# BrickPi_0_7.net
KiCad netlist of a schematic drawn in EAGLE
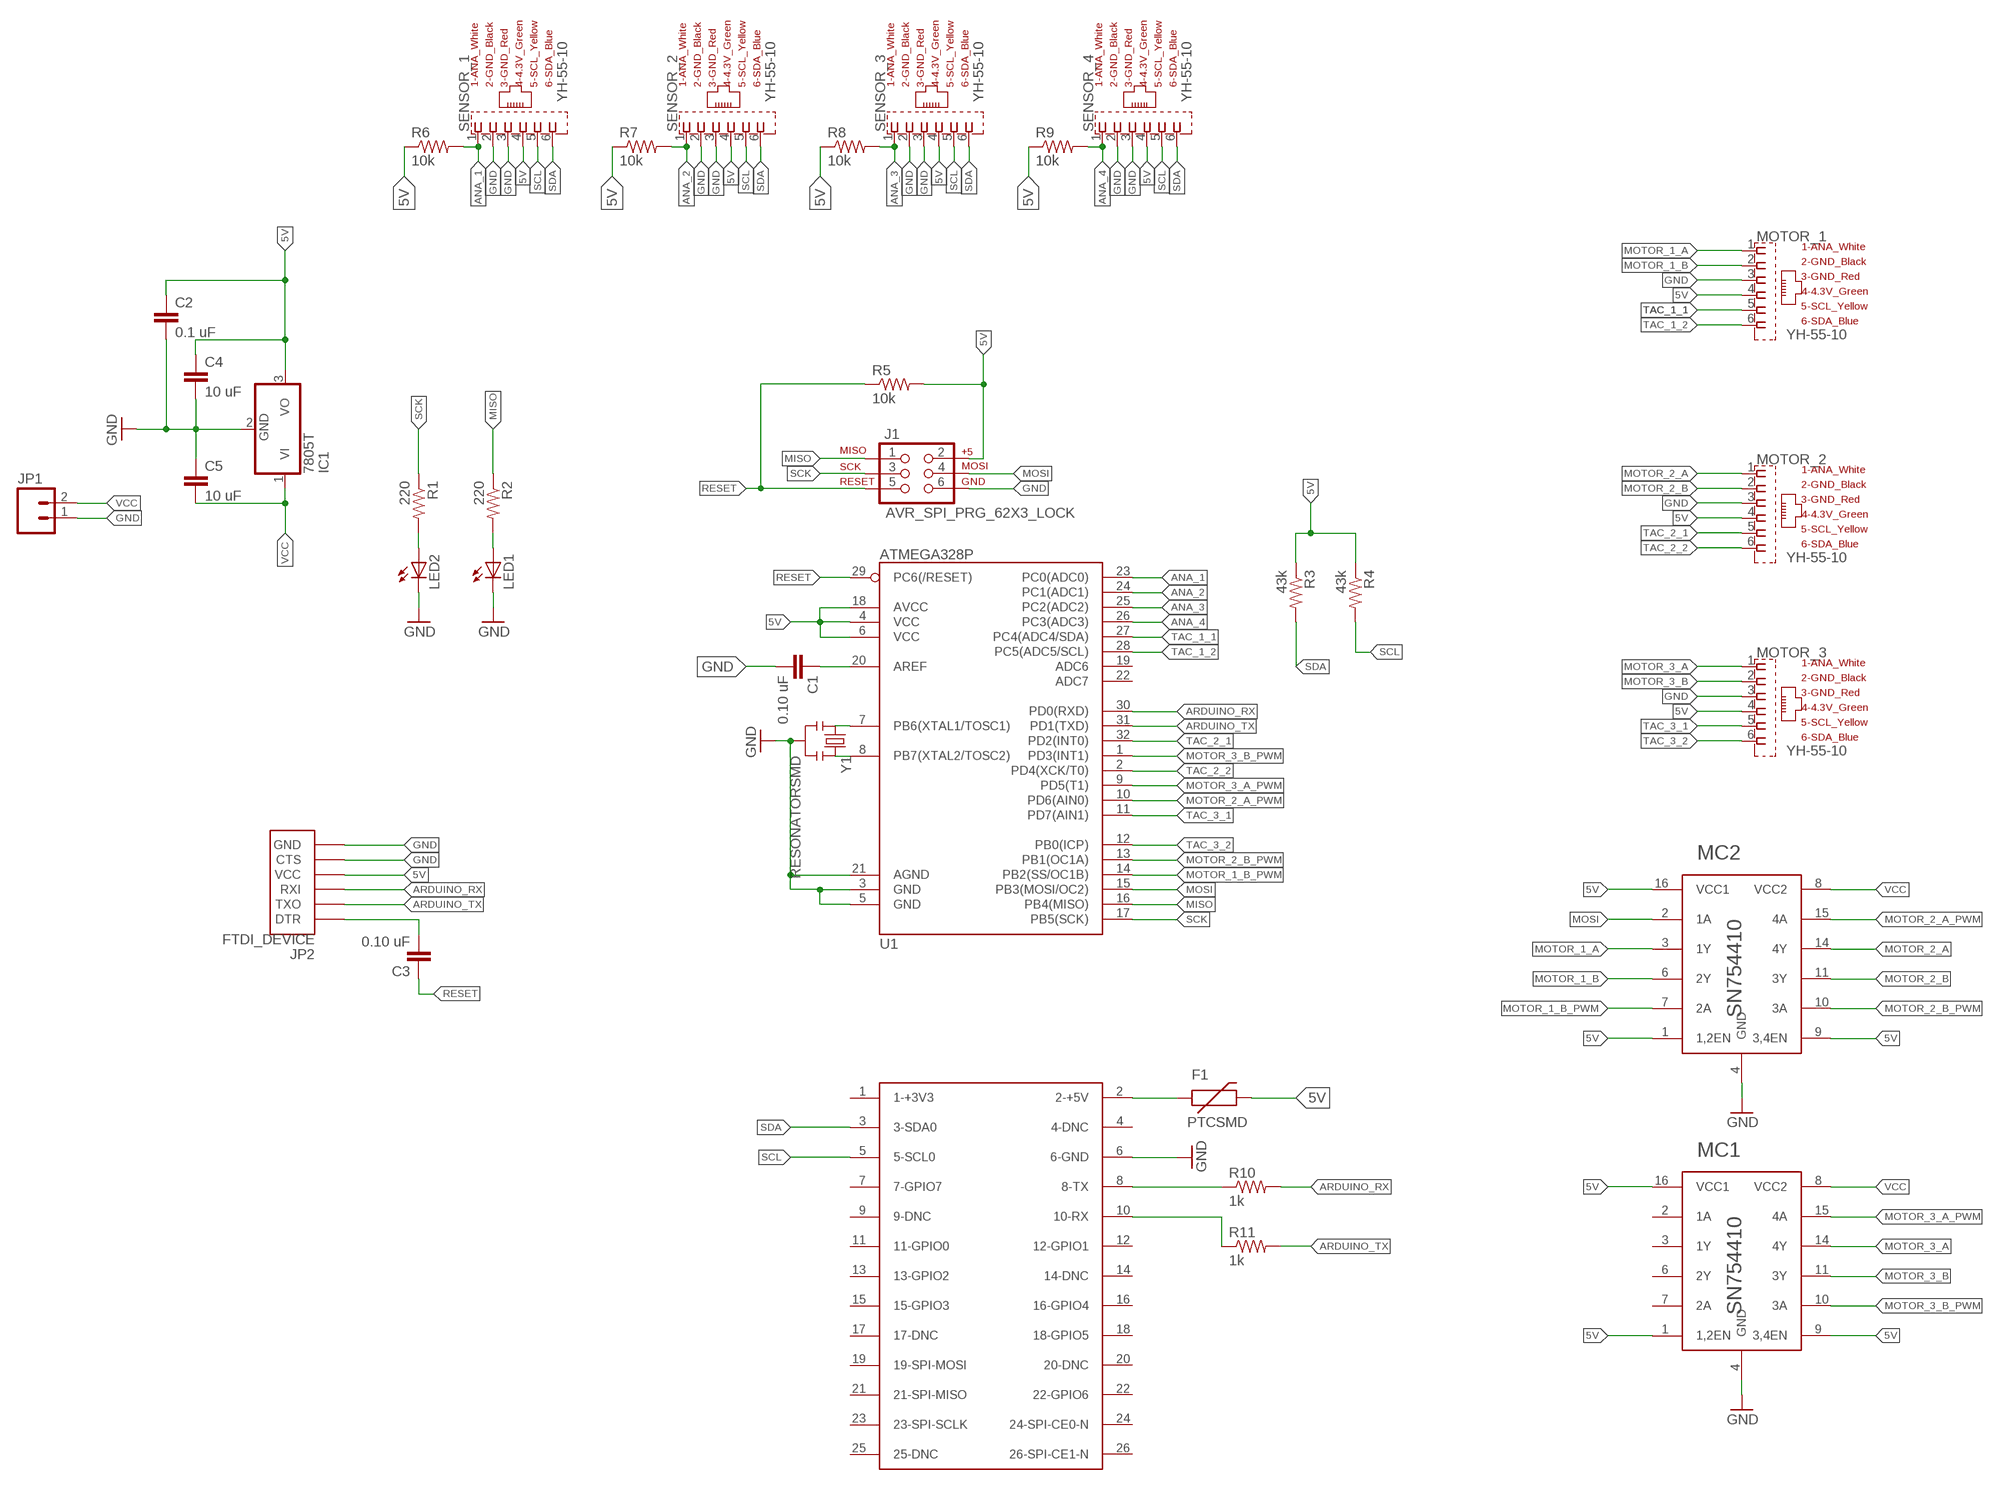
[diagram p0: schematic, sheet 1]

(export (version "E")
  (design (tool "Eeschema 10.0.6"))
  (components
    (comp (ref "C1")
      (value "0.10 uF")
      (footprint "eagle-import:0805")
      (libsource (lib "eagle-import") (part "CAP0805"))
    )
    (comp (ref "C2")
      (value "0.1 uF")
      (footprint "eagle-import:0805")
      (libsource (lib "eagle-import") (part "CAP0805"))
    )
    (comp (ref "C3")
      (value "0.10 uF")
      (footprint "eagle-import:0805")
      (libsource (lib "eagle-import") (part "CAP0805"))
    )
    (comp (ref "C4")
      (value "10 uF")
      (footprint "eagle-import:0805")
      (libsource (lib "eagle-import") (part "CAP0805"))
    )
    (comp (ref "C5")
      (value "10 uF")
      (footprint "eagle-import:0805")
      (libsource (lib "eagle-import") (part "CAP0805"))
    )
    (comp (ref "F1")
      (value "PTCSMD")
      (footprint "eagle-import:PTC-1206")
      (libsource (lib "eagle-import") (part "PTCSMD"))
    )
    (comp (ref "IC1")
      (value "7805T")
      (footprint "eagle-import:TO220H")
      (libsource (lib "eagle-import") (part "78T05"))
    )
    (comp (ref "J1")
      (value "AVR_SPI_PRG_62X3_LOCK")
      (footprint "eagle-import:2X3_LOCK")
      (libsource (lib "eagle-import") (part "AVR_SPI_PRG_62X3_LOCK"))
    )
    (comp (ref "JP1")
      (value "M02LOCK")
      (footprint "eagle-import:1X02_LOCK")
      (libsource (lib "eagle-import") (part "M02LOCK"))
    )
    (comp (ref "JP2")
      (value "FTDI_DEVICE")
      (footprint "eagle-import:FTDI_DEVICE_SIDE")
      (libsource (lib "eagle-import") (part "FTDI_DEVICE"))
    )
    (comp (ref "LED1")
      (value "LED1206")
      (footprint "eagle-import:LED-1206")
      (libsource (lib "eagle-import") (part "LED1206"))
    )
    (comp (ref "LED2")
      (value "LED1206")
      (footprint "eagle-import:LED-1206")
      (libsource (lib "eagle-import") (part "LED1206"))
    )
    (comp (ref "MC1")
      (value "SN754410")
      (footprint "eagle-import:DIL16")
      (libsource (lib "eagle-import") (part "SN754410"))
    )
    (comp (ref "MC2")
      (value "SN754410")
      (footprint "eagle-import:DIL16")
      (libsource (lib "eagle-import") (part "SN754410"))
    )
    (comp (ref "MOTOR_1")
      (value "YH-55-10")
      (footprint "eagle-import:YH-55-10")
      (libsource (lib "eagle-import") (part "YH-55-10"))
    )
    (comp (ref "MOTOR_2")
      (value "YH-55-10")
      (footprint "eagle-import:YH-55-10")
      (libsource (lib "eagle-import") (part "YH-55-10"))
    )
    (comp (ref "MOTOR_3")
      (value "YH-55-10")
      (footprint "eagle-import:YH-55-10")
      (libsource (lib "eagle-import") (part "YH-55-10"))
    )
    (comp (ref "PI_OUTLINE")
      (value "RASPBERRY-PI")
      (footprint "eagle-import:RASPBERRY-PI")
      (libsource (lib "eagle-import") (part "RASPBERRY-PI"))
    )
    (comp (ref "R1")
      (value "220")
      (footprint "eagle-import:0603-RES")
      (libsource (lib "eagle-import") (part "220-5%"))
    )
    (comp (ref "R2")
      (value "220")
      (footprint "eagle-import:0603-RES")
      (libsource (lib "eagle-import") (part "220-5%"))
    )
    (comp (ref "R3")
      (value "43k")
      (footprint "eagle-import:0603-RES")
      (fields (field (name "PROD_ID") "RES-07866"))
      (libsource (lib "eagle-import") (part "220-5%"))
    )
    (comp (ref "R4")
      (value "43k")
      (footprint "eagle-import:0603-RES")
      (fields (field (name "PROD_ID") "RES-07866"))
      (libsource (lib "eagle-import") (part "220-5%"))
    )
    (comp (ref "R5")
      (value "10k")
      (footprint "eagle-import:0603-RES")
      (fields (field (name "PROD_ID") "RES-07866"))
      (libsource (lib "eagle-import") (part "220-5%"))
    )
    (comp (ref "R6")
      (value "10k")
      (footprint "eagle-import:0603-RES")
      (fields (field (name "PROD_ID") "RES-07866"))
      (libsource (lib "eagle-import") (part "220-5%"))
    )
    (comp (ref "R7")
      (value "10k")
      (footprint "eagle-import:0603-RES")
      (fields (field (name "PROD_ID") "RES-07866"))
      (libsource (lib "eagle-import") (part "220-5%"))
    )
    (comp (ref "R8")
      (value "10k")
      (footprint "eagle-import:0603-RES")
      (fields (field (name "PROD_ID") "RES-07866"))
      (libsource (lib "eagle-import") (part "220-5%"))
    )
    (comp (ref "R9")
      (value "10k")
      (footprint "eagle-import:0603-RES")
      (fields (field (name "PROD_ID") "RES-07866"))
      (libsource (lib "eagle-import") (part "220-5%"))
    )
    (comp (ref "R10")
      (value "1k")
      (footprint "eagle-import:0603-RES")
      (fields (field (name "PROD_ID") "RES-07866"))
      (libsource (lib "eagle-import") (part "220-5%"))
    )
    (comp (ref "R11")
      (value "1k")
      (footprint "eagle-import:0603-RES")
      (fields (field (name "PROD_ID") "RES-07866"))
      (libsource (lib "eagle-import") (part "220-5%"))
    )
    (comp (ref "SENSOR_1")
      (value "YH-55-10")
      (footprint "eagle-import:YH-55-10")
      (libsource (lib "eagle-import") (part "YH-55-10"))
    )
    (comp (ref "SENSOR_2")
      (value "YH-55-10")
      (footprint "eagle-import:YH-55-10")
      (libsource (lib "eagle-import") (part "YH-55-10"))
    )
    (comp (ref "SENSOR_3")
      (value "YH-55-10")
      (footprint "eagle-import:YH-55-10")
      (libsource (lib "eagle-import") (part "YH-55-10"))
    )
    (comp (ref "SENSOR_4")
      (value "YH-55-10")
      (footprint "eagle-import:YH-55-10")
      (libsource (lib "eagle-import") (part "YH-55-10"))
    )
    (comp (ref "U1")
      (value "ATMEGA328P")
      (footprint "eagle-import:TQFP32-08")
      (libsource (lib "eagle-import") (part "ATMEGA328_SMT"))
    )
    (comp (ref "Y1")
      (value "RESONATORSMD")
      (footprint "eagle-import:RESONATOR-SMD")
      (libsource (lib "eagle-import") (part "RESONATORSMD"))
    )
  )
  (nets
    (net (code "1") (name "5V") (class "Default")
      (node (ref "C2") (pin "1") (pinfunction "1_1") (pintype "passive"))
      (node (ref "C4") (pin "1") (pinfunction "1_1") (pintype "passive"))
      (node (ref "F1") (pin "2") (pinfunction "2_2") (pintype "bidirectional"))
      (node (ref "IC1") (pin "3") (pinfunction "VO_3") (pintype "passive"))
      (node (ref "J1") (pin "2") (pinfunction "2_2") (pintype "passive"))
      (node (ref "JP2") (pin "P$4") (pinfunction "VCC_P$4") (pintype "bidirectional"))
      (node (ref "MC1") (pin "1") (pinfunction "1,2EN_1") (pintype "bidirectional"))
      (node (ref "MC1") (pin "16") (pinfunction "VCC1_16") (pintype "power_in"))
      (node (ref "MC1") (pin "9") (pinfunction "3,4EN_9") (pintype "bidirectional"))
      (node (ref "MC2") (pin "1") (pinfunction "1,2EN_1") (pintype "bidirectional"))
      (node (ref "MC2") (pin "16") (pinfunction "VCC1_16") (pintype "power_in"))
      (node (ref "MC2") (pin "9") (pinfunction "3,4EN_9") (pintype "bidirectional"))
      (node (ref "MOTOR_1") (pin "4") (pinfunction "4_4.3V_GREEN_4") (pintype "passive"))
      (node (ref "MOTOR_2") (pin "4") (pinfunction "4_4.3V_GREEN_4") (pintype "passive"))
      (node (ref "MOTOR_3") (pin "4") (pinfunction "4_4.3V_GREEN_4") (pintype "passive"))
      (node (ref "R3") (pin "1") (pinfunction "1_1") (pintype "passive"))
      (node (ref "R4") (pin "1") (pinfunction "1_1") (pintype "passive"))
      (node (ref "R5") (pin "2") (pinfunction "2_2") (pintype "passive"))
      (node (ref "R6") (pin "1") (pinfunction "1_1") (pintype "passive"))
      (node (ref "R7") (pin "1") (pinfunction "1_1") (pintype "passive"))
      (node (ref "R8") (pin "1") (pinfunction "1_1") (pintype "passive"))
      (node (ref "R9") (pin "1") (pinfunction "1_1") (pintype "passive"))
      (node (ref "SENSOR_1") (pin "4") (pinfunction "4_4.3V_GREEN_4") (pintype "passive"))
      (node (ref "SENSOR_2") (pin "4") (pinfunction "4_4.3V_GREEN_4") (pintype "passive"))
      (node (ref "SENSOR_3") (pin "4") (pinfunction "4_4.3V_GREEN_4") (pintype "passive"))
      (node (ref "SENSOR_4") (pin "4") (pinfunction "4_4.3V_GREEN_4") (pintype "passive"))
      (node (ref "U1") (pin "18") (pinfunction "AVCC_18") (pintype "bidirectional"))
      (node (ref "U1") (pin "4") (pinfunction "VCC_4") (pintype "bidirectional"))
      (node (ref "U1") (pin "6") (pinfunction "VCC_6") (pintype "bidirectional"))
    )
    (net (code "2") (name "ANA_1") (class "Default")
      (node (ref "R6") (pin "2") (pinfunction "2_2") (pintype "passive"))
      (node (ref "SENSOR_1") (pin "1") (pinfunction "1_ANA_WHITE_1") (pintype "passive"))
      (node (ref "U1") (pin "23") (pinfunction "PC0(ADC0)_23") (pintype "bidirectional"))
    )
    (net (code "3") (name "ANA_2") (class "Default")
      (node (ref "R7") (pin "2") (pinfunction "2_2") (pintype "passive"))
      (node (ref "SENSOR_2") (pin "1") (pinfunction "1_ANA_WHITE_1") (pintype "passive"))
      (node (ref "U1") (pin "24") (pinfunction "PC1(ADC1)_24") (pintype "bidirectional"))
    )
    (net (code "4") (name "ANA_3") (class "Default")
      (node (ref "R8") (pin "2") (pinfunction "2_2") (pintype "passive"))
      (node (ref "SENSOR_3") (pin "1") (pinfunction "1_ANA_WHITE_1") (pintype "passive"))
      (node (ref "U1") (pin "25") (pinfunction "PC2(ADC2)_25") (pintype "bidirectional"))
    )
    (net (code "5") (name "ANA_4") (class "Default")
      (node (ref "R9") (pin "2") (pinfunction "2_2") (pintype "passive"))
      (node (ref "SENSOR_4") (pin "1") (pinfunction "1_ANA_WHITE_1") (pintype "passive"))
      (node (ref "U1") (pin "26") (pinfunction "PC3(ADC3)_26") (pintype "bidirectional"))
    )
    (net (code "6") (name "ARDUINO_RX") (class "Default")
      (node (ref "JP2") (pin "P$3") (pinfunction "RXI_P$3") (pintype "bidirectional"))
      (node (ref "R10") (pin "2") (pinfunction "2_2") (pintype "passive"))
      (node (ref "U1") (pin "30") (pinfunction "PD0(RXD)_30") (pintype "bidirectional"))
    )
    (net (code "7") (name "ARDUINO_TX") (class "Default")
      (node (ref "JP2") (pin "P$2") (pinfunction "TXO_P$2") (pintype "bidirectional"))
      (node (ref "R11") (pin "2") (pinfunction "2_2") (pintype "passive"))
      (node (ref "U1") (pin "31") (pinfunction "PD1(TXD)_31") (pintype "bidirectional"))
    )
    (net (code "8") (name "GND") (class "Default")
      (node (ref "C1") (pin "2") (pinfunction "2_2") (pintype "passive"))
      (node (ref "C2") (pin "2") (pinfunction "2_2") (pintype "passive"))
      (node (ref "C4") (pin "2") (pinfunction "2_2") (pintype "passive"))
      (node (ref "C5") (pin "1") (pinfunction "1_1") (pintype "passive"))
      (node (ref "IC1") (pin "2") (pinfunction "GND_2") (pintype "passive"))
      (node (ref "J1") (pin "6") (pinfunction "6_6") (pintype "passive"))
      (node (ref "JP1") (pin "1") (pinfunction "1_1") (pintype "passive"))
      (node (ref "JP2") (pin "P$5") (pinfunction "CTS_P$5") (pintype "bidirectional"))
      (node (ref "JP2") (pin "P$6") (pinfunction "GND_P$6") (pintype "bidirectional"))
      (node (ref "LED1") (pin "C") (pinfunction "C_C") (pintype "passive"))
      (node (ref "LED2") (pin "C") (pinfunction "C_C") (pintype "passive"))
      (node (ref "MC1") (pin "4") (pinfunction "GND_4") (pintype "power_in"))
      (node (ref "MC2") (pin "4") (pinfunction "GND_4") (pintype "power_in"))
      (node (ref "MOTOR_1") (pin "3") (pinfunction "3_GND_RED_3") (pintype "passive"))
      (node (ref "MOTOR_2") (pin "3") (pinfunction "3_GND_RED_3") (pintype "passive"))
      (node (ref "MOTOR_3") (pin "3") (pinfunction "3_GND_RED_3") (pintype "passive"))
      (node (ref "PI_OUTLINE") (pin "6") (pinfunction "6-GND_6") (pintype "bidirectional"))
      (node (ref "SENSOR_1") (pin "2") (pinfunction "2_GND_BLACK_2") (pintype "passive"))
      (node (ref "SENSOR_1") (pin "3") (pinfunction "3_GND_RED_3") (pintype "passive"))
      (node (ref "SENSOR_2") (pin "2") (pinfunction "2_GND_BLACK_2") (pintype "passive"))
      (node (ref "SENSOR_2") (pin "3") (pinfunction "3_GND_RED_3") (pintype "passive"))
      (node (ref "SENSOR_3") (pin "2") (pinfunction "2_GND_BLACK_2") (pintype "passive"))
      (node (ref "SENSOR_3") (pin "3") (pinfunction "3_GND_RED_3") (pintype "passive"))
      (node (ref "SENSOR_4") (pin "2") (pinfunction "2_GND_BLACK_2") (pintype "passive"))
      (node (ref "SENSOR_4") (pin "3") (pinfunction "3_GND_RED_3") (pintype "passive"))
      (node (ref "U1") (pin "21") (pinfunction "AGND_21") (pintype "bidirectional"))
      (node (ref "U1") (pin "3") (pinfunction "GND_3") (pintype "bidirectional"))
      (node (ref "U1") (pin "5") (pinfunction "GND_5") (pintype "bidirectional"))
      (node (ref "Y1") (pin "2") (pinfunction "2_2") (pintype "passive"))
    )
    (net (code "9") (name "MISO") (class "Default")
      (node (ref "J1") (pin "1") (pinfunction "1_1") (pintype "passive"))
      (node (ref "R2") (pin "1") (pinfunction "1_1") (pintype "passive"))
      (node (ref "U1") (pin "16") (pinfunction "PB4(MISO)_16") (pintype "bidirectional"))
    )
    (net (code "10") (name "MOSI") (class "Default")
      (node (ref "J1") (pin "4") (pinfunction "4_4") (pintype "passive"))
      (node (ref "MC2") (pin "2") (pinfunction "1A_2") (pintype "bidirectional"))
      (node (ref "U1") (pin "15") (pinfunction "PB3(MOSI/OC2)_15") (pintype "bidirectional"))
    )
    (net (code "11") (name "MOTOR_1_A") (class "Default")
      (node (ref "MC2") (pin "3") (pinfunction "1Y_3") (pintype "bidirectional"))
      (node (ref "MOTOR_1") (pin "1") (pinfunction "1_ANA_WHITE_1") (pintype "passive"))
    )
    (net (code "12") (name "MOTOR_1_B") (class "Default")
      (node (ref "MC2") (pin "6") (pinfunction "2Y_6") (pintype "bidirectional"))
      (node (ref "MOTOR_1") (pin "2") (pinfunction "2_GND_BLACK_2") (pintype "passive"))
    )
    (net (code "13") (name "MOTOR_1_B_PWM") (class "Default")
      (node (ref "MC2") (pin "7") (pinfunction "2A_7") (pintype "bidirectional"))
      (node (ref "U1") (pin "14") (pinfunction "PB2(SS/OC1B)_14") (pintype "bidirectional"))
    )
    (net (code "14") (name "MOTOR_2_A") (class "Default")
      (node (ref "MC2") (pin "14") (pinfunction "4Y_14") (pintype "bidirectional"))
      (node (ref "MOTOR_2") (pin "1") (pinfunction "1_ANA_WHITE_1") (pintype "passive"))
    )
    (net (code "15") (name "MOTOR_2_A_PWM") (class "Default")
      (node (ref "MC2") (pin "15") (pinfunction "4A_15") (pintype "bidirectional"))
      (node (ref "U1") (pin "10") (pinfunction "PD6(AIN0)_10") (pintype "bidirectional"))
    )
    (net (code "16") (name "MOTOR_2_B") (class "Default")
      (node (ref "MC2") (pin "11") (pinfunction "3Y_11") (pintype "bidirectional"))
      (node (ref "MOTOR_2") (pin "2") (pinfunction "2_GND_BLACK_2") (pintype "passive"))
    )
    (net (code "17") (name "MOTOR_2_B_PWM") (class "Default")
      (node (ref "MC2") (pin "10") (pinfunction "3A_10") (pintype "bidirectional"))
      (node (ref "U1") (pin "13") (pinfunction "PB1(OC1A)_13") (pintype "bidirectional"))
    )
    (net (code "18") (name "MOTOR_3_A") (class "Default")
      (node (ref "MC1") (pin "14") (pinfunction "4Y_14") (pintype "bidirectional"))
      (node (ref "MOTOR_3") (pin "1") (pinfunction "1_ANA_WHITE_1") (pintype "passive"))
    )
    (net (code "19") (name "MOTOR_3_A_PWM") (class "Default")
      (node (ref "MC1") (pin "15") (pinfunction "4A_15") (pintype "bidirectional"))
      (node (ref "U1") (pin "9") (pinfunction "PD5(T1)_9") (pintype "bidirectional"))
    )
    (net (code "20") (name "MOTOR_3_B") (class "Default")
      (node (ref "MC1") (pin "11") (pinfunction "3Y_11") (pintype "bidirectional"))
      (node (ref "MOTOR_3") (pin "2") (pinfunction "2_GND_BLACK_2") (pintype "passive"))
    )
    (net (code "21") (name "MOTOR_3_B_PWM") (class "Default")
      (node (ref "MC1") (pin "10") (pinfunction "3A_10") (pintype "bidirectional"))
      (node (ref "U1") (pin "1") (pinfunction "PD3(INT1)_1") (pintype "bidirectional"))
    )
    (net (code "22") (name "Net-(JP2-DTR)") (class "Default")
      (node (ref "C3") (pin "2") (pinfunction "2_2") (pintype "passive"))
      (node (ref "JP2") (pin "P$1") (pinfunction "DTR_P$1") (pintype "bidirectional"))
    )
    (net (code "23") (name "Net-(LED1-PadA)") (class "Default")
      (node (ref "LED1") (pin "A") (pinfunction "A_A") (pintype "passive"))
      (node (ref "R2") (pin "2") (pinfunction "2_2") (pintype "passive"))
    )
    (net (code "24") (name "Net-(LED2-PadA)") (class "Default")
      (node (ref "LED2") (pin "A") (pinfunction "A_A") (pintype "passive"))
      (node (ref "R1") (pin "2") (pinfunction "2_2") (pintype "passive"))
    )
    (net (code "25") (name "Net-(PI_OUTLINE-2-+5V)") (class "Default")
      (node (ref "F1") (pin "1") (pinfunction "1_1") (pintype "bidirectional"))
      (node (ref "PI_OUTLINE") (pin "2") (pinfunction "2-+5V_2") (pintype "bidirectional"))
    )
    (net (code "26") (name "Net-(PI_OUTLINE-8-TX)") (class "Default")
      (node (ref "PI_OUTLINE") (pin "8") (pinfunction "8-TX_8") (pintype "bidirectional"))
      (node (ref "R10") (pin "1") (pinfunction "1_1") (pintype "passive"))
    )
    (net (code "27") (name "Net-(PI_OUTLINE-10-RX)") (class "Default")
      (node (ref "PI_OUTLINE") (pin "10") (pinfunction "10-RX_10") (pintype "bidirectional"))
      (node (ref "R11") (pin "1") (pinfunction "1_1") (pintype "passive"))
    )
    (net (code "28") (name "Net-(U1-AREF)") (class "Default")
      (node (ref "C1") (pin "1") (pinfunction "1_1") (pintype "passive"))
      (node (ref "U1") (pin "20") (pinfunction "AREF_20") (pintype "bidirectional"))
    )
    (net (code "29") (name "Net-(U1-PB6(XTAL1{slash}TOSC1))") (class "Default")
      (node (ref "U1") (pin "7") (pinfunction "PB6(XTAL1/TOSC1)_7") (pintype "bidirectional"))
      (node (ref "Y1") (pin "1") (pinfunction "1_1") (pintype "passive"))
    )
    (net (code "30") (name "Net-(U1-PB7(XTAL2{slash}TOSC2))") (class "Default")
      (node (ref "U1") (pin "8") (pinfunction "PB7(XTAL2/TOSC2)_8") (pintype "bidirectional"))
      (node (ref "Y1") (pin "3") (pinfunction "3_3") (pintype "passive"))
    )
    (net (code "31") (name "RESET") (class "Default")
      (node (ref "C3") (pin "1") (pinfunction "1_1") (pintype "passive"))
      (node (ref "J1") (pin "5") (pinfunction "5_5") (pintype "passive"))
      (node (ref "R5") (pin "1") (pinfunction "1_1") (pintype "passive"))
      (node (ref "U1") (pin "29") (pinfunction "PC6(/RESET)_29") (pintype "bidirectional"))
    )
    (net (code "32") (name "SCK") (class "Default")
      (node (ref "J1") (pin "3") (pinfunction "3_3") (pintype "passive"))
      (node (ref "R1") (pin "1") (pinfunction "1_1") (pintype "passive"))
      (node (ref "U1") (pin "17") (pinfunction "PB5(SCK)_17") (pintype "bidirectional"))
    )
    (net (code "33") (name "SCL") (class "Default")
      (node (ref "PI_OUTLINE") (pin "5") (pinfunction "5-SCL0_5") (pintype "bidirectional"))
      (node (ref "R4") (pin "2") (pinfunction "2_2") (pintype "passive"))
      (node (ref "SENSOR_1") (pin "5") (pinfunction "5_SCL_YELLOW_5") (pintype "passive"))
      (node (ref "SENSOR_2") (pin "5") (pinfunction "5_SCL_YELLOW_5") (pintype "passive"))
      (node (ref "SENSOR_3") (pin "5") (pinfunction "5_SCL_YELLOW_5") (pintype "passive"))
      (node (ref "SENSOR_4") (pin "5") (pinfunction "5_SCL_YELLOW_5") (pintype "passive"))
    )
    (net (code "34") (name "SDA") (class "Default")
      (node (ref "PI_OUTLINE") (pin "3") (pinfunction "3-SDA0_3") (pintype "bidirectional"))
      (node (ref "R3") (pin "2") (pinfunction "2_2") (pintype "passive"))
      (node (ref "SENSOR_1") (pin "6") (pinfunction "6_SDA_BLUE_6") (pintype "passive"))
      (node (ref "SENSOR_2") (pin "6") (pinfunction "6_SDA_BLUE_6") (pintype "passive"))
      (node (ref "SENSOR_3") (pin "6") (pinfunction "6_SDA_BLUE_6") (pintype "passive"))
      (node (ref "SENSOR_4") (pin "6") (pinfunction "6_SDA_BLUE_6") (pintype "passive"))
    )
    (net (code "35") (name "TAC_1_1") (class "Default")
      (node (ref "MOTOR_1") (pin "5") (pinfunction "5_SCL_YELLOW_5") (pintype "passive"))
      (node (ref "U1") (pin "27") (pinfunction "PC4(ADC4/SDA)_27") (pintype "bidirectional"))
    )
    (net (code "36") (name "TAC_1_2") (class "Default")
      (node (ref "MOTOR_1") (pin "6") (pinfunction "6_SDA_BLUE_6") (pintype "passive"))
      (node (ref "U1") (pin "28") (pinfunction "PC5(ADC5/SCL)_28") (pintype "bidirectional"))
    )
    (net (code "37") (name "TAC_2_1") (class "Default")
      (node (ref "MOTOR_2") (pin "5") (pinfunction "5_SCL_YELLOW_5") (pintype "passive"))
      (node (ref "U1") (pin "32") (pinfunction "PD2(INT0)_32") (pintype "bidirectional"))
    )
    (net (code "38") (name "TAC_2_2") (class "Default")
      (node (ref "MOTOR_2") (pin "6") (pinfunction "6_SDA_BLUE_6") (pintype "passive"))
      (node (ref "U1") (pin "2") (pinfunction "PD4(XCK/T0)_2") (pintype "bidirectional"))
    )
    (net (code "39") (name "TAC_3_1") (class "Default")
      (node (ref "MOTOR_3") (pin "5") (pinfunction "5_SCL_YELLOW_5") (pintype "passive"))
      (node (ref "U1") (pin "11") (pinfunction "PD7(AIN1)_11") (pintype "bidirectional"))
    )
    (net (code "40") (name "TAC_3_2") (class "Default")
      (node (ref "MOTOR_3") (pin "6") (pinfunction "6_SDA_BLUE_6") (pintype "passive"))
      (node (ref "U1") (pin "12") (pinfunction "PB0(ICP)_12") (pintype "bidirectional"))
    )
    (net (code "41") (name "VCC") (class "Default")
      (node (ref "C5") (pin "2") (pinfunction "2_2") (pintype "passive"))
      (node (ref "IC1") (pin "1") (pinfunction "VI_1") (pintype "input"))
      (node (ref "JP1") (pin "2") (pinfunction "2_2") (pintype "passive"))
      (node (ref "MC1") (pin "8") (pinfunction "VCC2_8") (pintype "power_in"))
      (node (ref "MC2") (pin "8") (pinfunction "VCC2_8") (pintype "power_in"))
    )
    (net (code "42") (name "unconnected-(MC1A-1A-Pad2)") (class "Default")
      (node (ref "MC1") (pin "2") (pinfunction "1A_2") (pintype "bidirectional"))
    )
    (net (code "43") (name "unconnected-(MC1A-1Y-Pad3)") (class "Default")
      (node (ref "MC1") (pin "3") (pinfunction "1Y_3") (pintype "bidirectional"))
    )
    (net (code "44") (name "unconnected-(MC1A-2A-Pad7)") (class "Default")
      (node (ref "MC1") (pin "7") (pinfunction "2A_7") (pintype "bidirectional"))
    )
    (net (code "45") (name "unconnected-(MC1A-2Y-Pad6)") (class "Default")
      (node (ref "MC1") (pin "6") (pinfunction "2Y_6") (pintype "bidirectional"))
    )
    (net (code "46") (name "unconnected-(PI_OUTLINE-1-+3V3-Pad1)") (class "Default")
      (node (ref "PI_OUTLINE") (pin "1") (pinfunction "1-+3V3_1") (pintype "bidirectional"))
    )
    (net (code "47") (name "unconnected-(PI_OUTLINE-4-DNC-Pad4)") (class "Default")
      (node (ref "PI_OUTLINE") (pin "4") (pinfunction "4-DNC_4") (pintype "bidirectional"))
    )
    (net (code "48") (name "unconnected-(PI_OUTLINE-7-GPIO7-Pad7)") (class "Default")
      (node (ref "PI_OUTLINE") (pin "7") (pinfunction "7-GPIO7_7") (pintype "bidirectional"))
    )
    (net (code "49") (name "unconnected-(PI_OUTLINE-9-DNC-Pad9)") (class "Default")
      (node (ref "PI_OUTLINE") (pin "9") (pinfunction "9-DNC_9") (pintype "bidirectional"))
    )
    (net (code "50") (name "unconnected-(PI_OUTLINE-11-GPIO0-Pad11)") (class "Default")
      (node (ref "PI_OUTLINE") (pin "11") (pinfunction "11-GPIO0_11") (pintype "bidirectional"))
    )
    (net (code "51") (name "unconnected-(PI_OUTLINE-12-GPIO1-Pad12)") (class "Default")
      (node (ref "PI_OUTLINE") (pin "12") (pinfunction "12-GPIO1_12") (pintype "bidirectional"))
    )
    (net (code "52") (name "unconnected-(PI_OUTLINE-13-GPIO2-Pad13)") (class "Default")
      (node (ref "PI_OUTLINE") (pin "13") (pinfunction "13-GPIO2_13") (pintype "bidirectional"))
    )
    (net (code "53") (name "unconnected-(PI_OUTLINE-14-DNC-Pad14)") (class "Default")
      (node (ref "PI_OUTLINE") (pin "14") (pinfunction "14-DNC_14") (pintype "bidirectional"))
    )
    (net (code "54") (name "unconnected-(PI_OUTLINE-15-GPIO3-Pad15)") (class "Default")
      (node (ref "PI_OUTLINE") (pin "15") (pinfunction "15-GPIO3_15") (pintype "bidirectional"))
    )
    (net (code "55") (name "unconnected-(PI_OUTLINE-16-GPIO4-Pad16)") (class "Default")
      (node (ref "PI_OUTLINE") (pin "16") (pinfunction "16-GPIO4_16") (pintype "bidirectional"))
    )
    (net (code "56") (name "unconnected-(PI_OUTLINE-17-DNC-Pad17)") (class "Default")
      (node (ref "PI_OUTLINE") (pin "17") (pinfunction "17-DNC_17") (pintype "bidirectional"))
    )
    (net (code "57") (name "unconnected-(PI_OUTLINE-18-GPIO5-Pad18)") (class "Default")
      (node (ref "PI_OUTLINE") (pin "18") (pinfunction "18-GPIO5_18") (pintype "bidirectional"))
    )
    (net (code "58") (name "unconnected-(PI_OUTLINE-19-SPI-MOSI-Pad19)") (class "Default")
      (node (ref "PI_OUTLINE") (pin "19") (pinfunction "19-SPI-MOSI_19") (pintype "bidirectional"))
    )
    (net (code "59") (name "unconnected-(PI_OUTLINE-20-DNC-Pad20)") (class "Default")
      (node (ref "PI_OUTLINE") (pin "20") (pinfunction "20-DNC_20") (pintype "bidirectional"))
    )
    (net (code "60") (name "unconnected-(PI_OUTLINE-21-SPI-MISO-Pad21)") (class "Default")
      (node (ref "PI_OUTLINE") (pin "21") (pinfunction "21-SPI-MISO_21") (pintype "bidirectional"))
    )
    (net (code "61") (name "unconnected-(PI_OUTLINE-22-GPIO6-Pad22)") (class "Default")
      (node (ref "PI_OUTLINE") (pin "22") (pinfunction "22-GPIO6_22") (pintype "bidirectional"))
    )
    (net (code "62") (name "unconnected-(PI_OUTLINE-23-SPI-SCLK-Pad23)") (class "Default")
      (node (ref "PI_OUTLINE") (pin "23") (pinfunction "23-SPI-SCLK_23") (pintype "bidirectional"))
    )
    (net (code "63") (name "unconnected-(PI_OUTLINE-24-SPI-CE0-N-Pad24)") (class "Default")
      (node (ref "PI_OUTLINE") (pin "24") (pinfunction "24-SPI-CE0-N_24") (pintype "bidirectional"))
    )
    (net (code "64") (name "unconnected-(PI_OUTLINE-25-DNC-Pad25)") (class "Default")
      (node (ref "PI_OUTLINE") (pin "25") (pinfunction "25-DNC_25") (pintype "bidirectional"))
    )
    (net (code "65") (name "unconnected-(PI_OUTLINE-26-SPI-CE1-N-Pad26)") (class "Default")
      (node (ref "PI_OUTLINE") (pin "26") (pinfunction "26-SPI-CE1-N_26") (pintype "bidirectional"))
    )
    (net (code "66") (name "unconnected-(U1-ADC6-Pad19)") (class "Default")
      (node (ref "U1") (pin "19") (pinfunction "ADC6_19") (pintype "bidirectional"))
    )
    (net (code "67") (name "unconnected-(U1-ADC7-Pad22)") (class "Default")
      (node (ref "U1") (pin "22") (pinfunction "ADC7_22") (pintype "bidirectional"))
    )
  )
)
